# BSPD_Main.net
KiCad netlist of a schematic drawn in Altium Designer
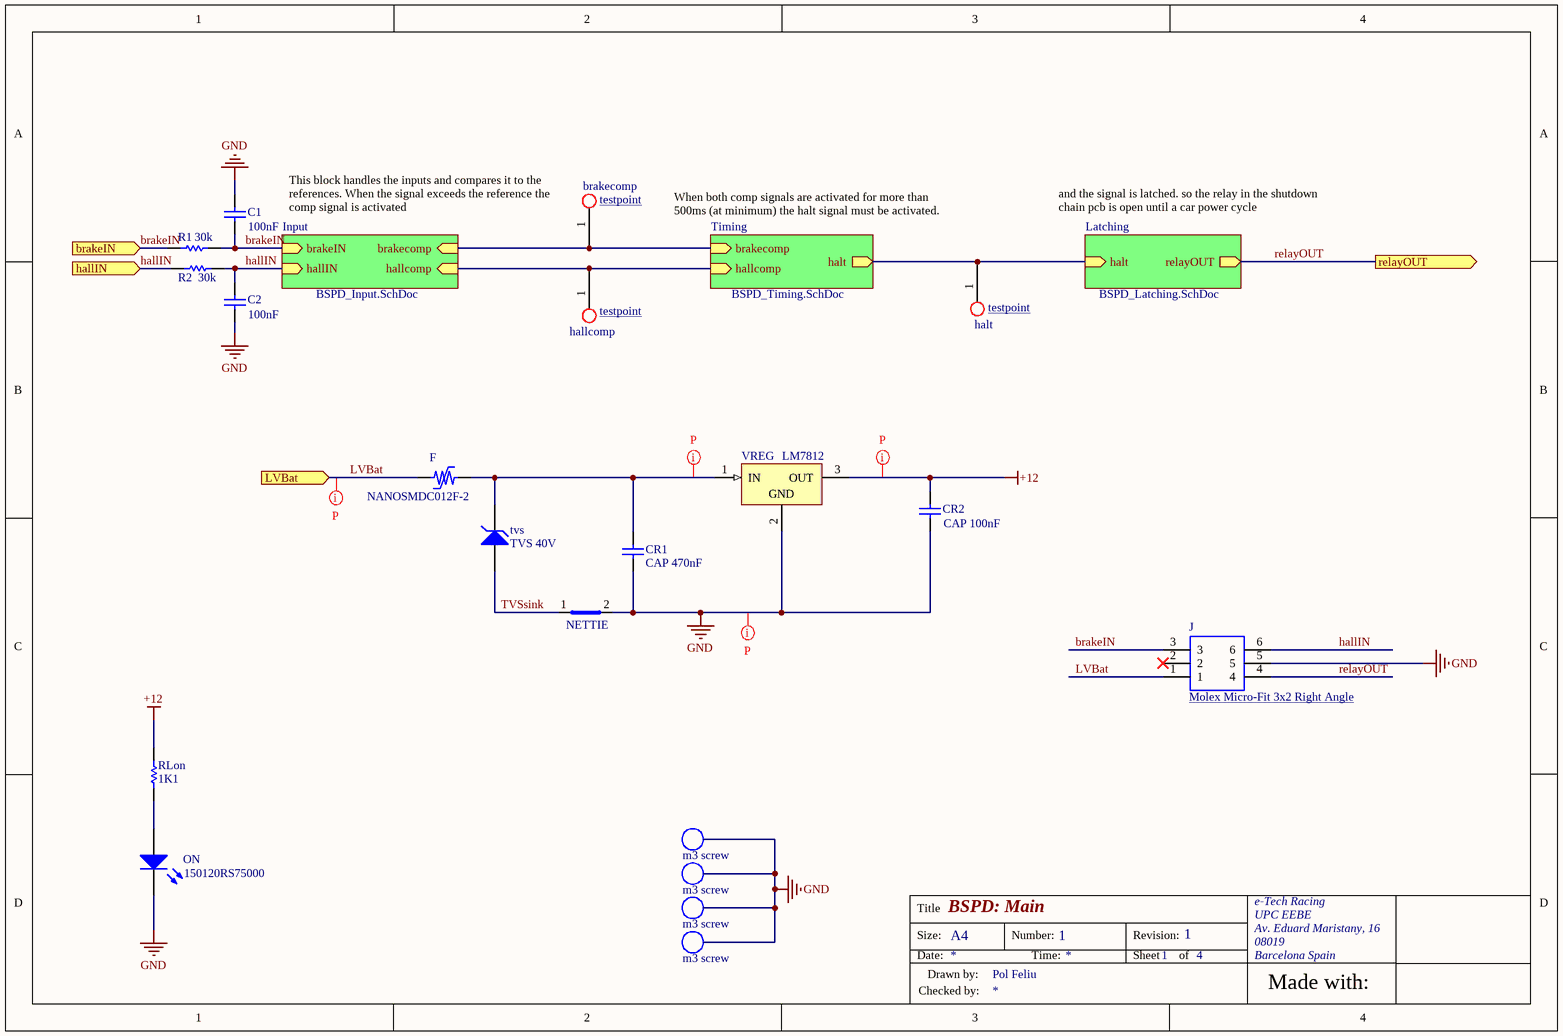
[diagram p0: BSPD_Main.SchDoc]

(export (version "E")
  (design (tool "Eeschema 10.0.6"))
  (components
    (comp (ref "brakecomp")
      (value "testpoint")
      (footprint "testpoint")
      (libsource (lib "LlibreriaEtech") (part "testpoint"))
    )
    (comp (ref "C1")
      (value "100nF")
      (footprint "CAPC0805(2012)145_M")
      (description "CAP 100nF 50V ±5% 0805 (2012 Metric) Thickness 1.45mm SMD")
      (fields (field (name "TOLERANCE") "Â±5%"))
      (libsource (lib "Altium Content Vault") (part "CAP"))
    )
    (comp (ref "C2")
      (value "100nF")
      (footprint "CAPC0805(2012)145_M")
      (description "CAP 100nF 50V ±5% 0805 (2012 Metric) Thickness 1.45mm SMD")
      (fields (field (name "TOLERANCE") "Â±5%"))
      (libsource (lib "Altium Content Vault") (part "CAP"))
    )
    (comp (ref "CR1")
      (value "CAP 470nF")
      (footprint "CAPC0805(2012)110_M")
      (description "CAP 470nF 50V ±20% 0805 (2012 Metric) Thickness 1.1mm SMD")
      (fields (field (name "TOLERANCE") "Â±20%"))
      (libsource (lib "Altium Content Vault") (part "CAP"))
    )
    (comp (ref "CR2")
      (value "CAP 100nF")
      (footprint "CAPC0805(2012)145_M")
      (description "CAP 100nF 50V ±5% 0805 (2012 Metric) Thickness 1.45mm SMD")
      (fields (field (name "TOLERANCE") "Â±5%"))
      (libsource (lib "Altium Content Vault") (part "CAP"))
    )
    (comp (ref "F")
      (value "NANOSMDC012F-2")
      (footprint "TECO-NANOSMDC012F_V")
      (description "PolySwitch Resettable Device, 0.12 A, 48 V, -40 to 85 degC, 2-Pin SMD, RoHS, Tape and Reel")
      (fields (field (name "MANUFACTURER") "TEConnectivity/CircuitProtection"))
      (libsource (lib "Altium Content Vault") (part "PPTC-2"))
    )
    (comp (ref "hallcomp")
      (value "testpoint")
      (footprint "testpoint")
      (libsource (lib "LlibreriaEtech") (part "testpoint"))
    )
    (comp (ref "halt")
      (value "testpoint")
      (footprint "testpoint")
      (libsource (lib "LlibreriaEtech") (part "testpoint"))
    )
    (comp (ref "J")
      (value "Molex Micro-Fit 3x2 Right Angle")
      (footprint "Molex Micro-fit 3x2 Right angle")
      (description "43045-0600")
      (libsource (lib "LlibreriaEtech") (part "Molex Micro-Fit 3x2 Right Angle"))
    )
    (comp (ref "m3screw1")
      (value "m3 screw")
      (footprint "M3 screw")
      (libsource (lib "Forats Cargols") (part "m3 screw"))
    )
    (comp (ref "m3screw2")
      (value "m3 screw")
      (footprint "M3 screw")
      (libsource (lib "Forats Cargols") (part "m3 screw"))
    )
    (comp (ref "m3screw3")
      (value "m3 screw")
      (footprint "M3 screw")
      (libsource (lib "Forats Cargols") (part "m3 screw"))
    )
    (comp (ref "m3screw4")
      (value "m3 screw")
      (footprint "M3 screw")
      (libsource (lib "Forats Cargols") (part "m3 screw"))
    )
    (comp (ref "nettie")
      (value "NETTIE")
      (footprint "NETTIE-SMT2-W0.8L2.0(MM)")
      (description "Net-Tie, Surface Mount, 2.0 mm x 0.8 mm, 2 Pads (1.2 mm x 0.8 mm)")
      (libsource (lib "Altium Content Vault") (part "NETTIE-2"))
    )
    (comp (ref "ON")
      (value "150120RS75000")
      (footprint "1206_A")
      (description "SMD mono-color Chip LED, WL-SMCW, Red")
      (fields (field (name "MANUFACTURER") "Wuerth Elektronik"))
      (libsource (lib "Altium Content Vault") (part "WE-LED_K1A2-2"))
    )
    (comp (ref "R1")
      (value "30k")
      (footprint "RESC3216X60X45LL10T20")
      (fields (field (name "MANUFACTURER") "Vishay Dale") (field (name "PART NUMBER") "CRCW120630K0JNEA"))
      (libsource (lib "Altium Content Vault") (part "RES"))
    )
    (comp (ref "R2")
      (value "30k")
      (footprint "RESC3216X60X45LL10T20")
      (description "CRCW120630K0JNEA")
      (fields (field (name "MANUFACTURER") "Vishay Dale"))
      (libsource (lib "Altium Content Vault") (part "RES"))
    )
    (comp (ref "RLon")
      (value "1K1")
      (footprint "RESC1206(3216)_M")
      (description "1K1 0.25W 5% 1206 (3216 Metric)  SMD")
      (fields (field (name "POWER") "0.25 W") (field (name "TOLERANCE") "5 %"))
      (libsource (lib "Altium Content Vault") (part "RES"))
    )
    (comp (ref "tvs")
      (value "TVS 40V")
      (footprint "TVS  DO-214AB")
      (fields
        (field (name "MANUFACTURER") "Wurth Electronics")
        (field (name "MANUFACTURER PART NUMBER") "824551401")
      )
      (libsource (lib "LlibreriaEtech") (part "TVS 40V"))
    )
    (comp (ref "VREG")
      (value "LM7812")
      (footprint "FAIR-TO-220-3")
      (description "Positive Voltage Regulator, 5 V, 1 A, -40 to 125 degC, 3-Pin TO-220, RoHS, Tube")
      (fields (field (name "MANUFACTURER") "FairchildSemiconductor"))
      (libsource (lib "Altium Content Vault") (part "FAIR-LM7805CT-TO220-3"))
    )
  )
  (nets
    (net (code "1") (name "+12") (class "Default")
      (node (ref "CR2") (pin "2") (pinfunction "2_2") (pintype "passive"))
      (node (ref "RLon") (pin "2") (pinfunction "2_2") (pintype "passive"))
      (node (ref "VREG") (pin "3") (pinfunction "OUT_3") (pintype "power_in"))
    )
    (net (code "2") (name "/LVBat") (class "Default")
      (node (ref "F") (pin "1") (pinfunction "1_1") (pintype "passive"))
      (node (ref "J") (pin "1") (pinfunction "1_1") (pintype "passive"))
    )
    (net (code "3") (name "/TVSsink") (class "Default")
      (node (ref "nettie") (pin "1") (pinfunction "Net1_1") (pintype "passive"))
      (node (ref "tvs") (pin "2") (pinfunction "A_2") (pintype "passive"))
    )
    (net (code "4") (name "/brakeIN") (class "Default")
      (node (ref "C1") (pin "1") (pinfunction "1_1") (pintype "passive"))
      (node (ref "J") (pin "3") (pinfunction "3_3") (pintype "passive"))
      (node (ref "R1") (pin "1") (pinfunction "1_1") (pintype "passive"))
      (node (ref "R1") (pin "2") (pinfunction "2_2") (pintype "passive"))
    )
    (net (code "5") (name "/brakecomp") (class "Default")
      (node (ref "brakecomp") (pin "1") (pinfunction "1_1") (pintype "passive"))
    )
    (net (code "6") (name "/hallIN") (class "Default")
      (node (ref "C2") (pin "2") (pinfunction "2_2") (pintype "passive"))
      (node (ref "J") (pin "6") (pinfunction "6_6") (pintype "passive"))
      (node (ref "R2") (pin "1") (pinfunction "1_1") (pintype "passive"))
      (node (ref "R2") (pin "2") (pinfunction "2_2") (pintype "passive"))
    )
    (net (code "7") (name "/hallcomp") (class "Default")
      (node (ref "hallcomp") (pin "1") (pinfunction "1_1") (pintype "passive"))
    )
    (net (code "8") (name "/halt") (class "Default")
      (node (ref "halt") (pin "1") (pinfunction "1_1") (pintype "passive"))
    )
    (net (code "9") (name "/relayOUT") (class "Default")
      (node (ref "J") (pin "4") (pinfunction "4_4") (pintype "passive"))
    )
    (net (code "10") (name "GND") (class "Default")
      (node (ref "C1") (pin "2") (pinfunction "2_2") (pintype "passive"))
      (node (ref "C2") (pin "1") (pinfunction "1_1") (pintype "passive"))
      (node (ref "CR1") (pin "1") (pinfunction "1_1") (pintype "passive"))
      (node (ref "CR2") (pin "1") (pinfunction "1_1") (pintype "passive"))
      (node (ref "J") (pin "5") (pinfunction "5_5") (pintype "passive"))
      (node (ref "ON") (pin "1") (pinfunction "K_1") (pintype "passive"))
      (node (ref "VREG") (pin "2") (pinfunction "GND_2") (pintype "power_in"))
      (node (ref "m3screw1") (pin "pad") (pinfunction "0_pad") (pintype "passive"))
      (node (ref "m3screw2") (pin "pad") (pinfunction "0_pad") (pintype "passive"))
      (node (ref "m3screw3") (pin "pad") (pinfunction "0_pad") (pintype "passive"))
      (node (ref "m3screw4") (pin "pad") (pinfunction "0_pad") (pintype "passive"))
      (node (ref "nettie") (pin "2") (pinfunction "Net2_2") (pintype "passive"))
    )
    (net (code "11") (name "Net-(ON-A)") (class "Default")
      (node (ref "ON") (pin "2") (pinfunction "A_2") (pintype "passive"))
      (node (ref "RLon") (pin "1") (pinfunction "1_1") (pintype "passive"))
    )
    (net (code "12") (name "Net-(VREG-IN)") (class "Default")
      (node (ref "CR1") (pin "2") (pinfunction "2_2") (pintype "passive"))
      (node (ref "F") (pin "2") (pinfunction "2_2") (pintype "passive"))
      (node (ref "VREG") (pin "1") (pinfunction "IN_1") (pintype "input"))
      (node (ref "tvs") (pin "1") (pinfunction "K_1") (pintype "passive"))
    )
    (net (code "13") (name "unconnected-(J-Pad2)") (class "Default")
      (node (ref "J") (pin "2") (pinfunction "2_2") (pintype "passive+no_connect"))
    )
  )
)
